# COM-Radio-SBand.net
KiCad netlist of a schematic drawn in Altium Designer
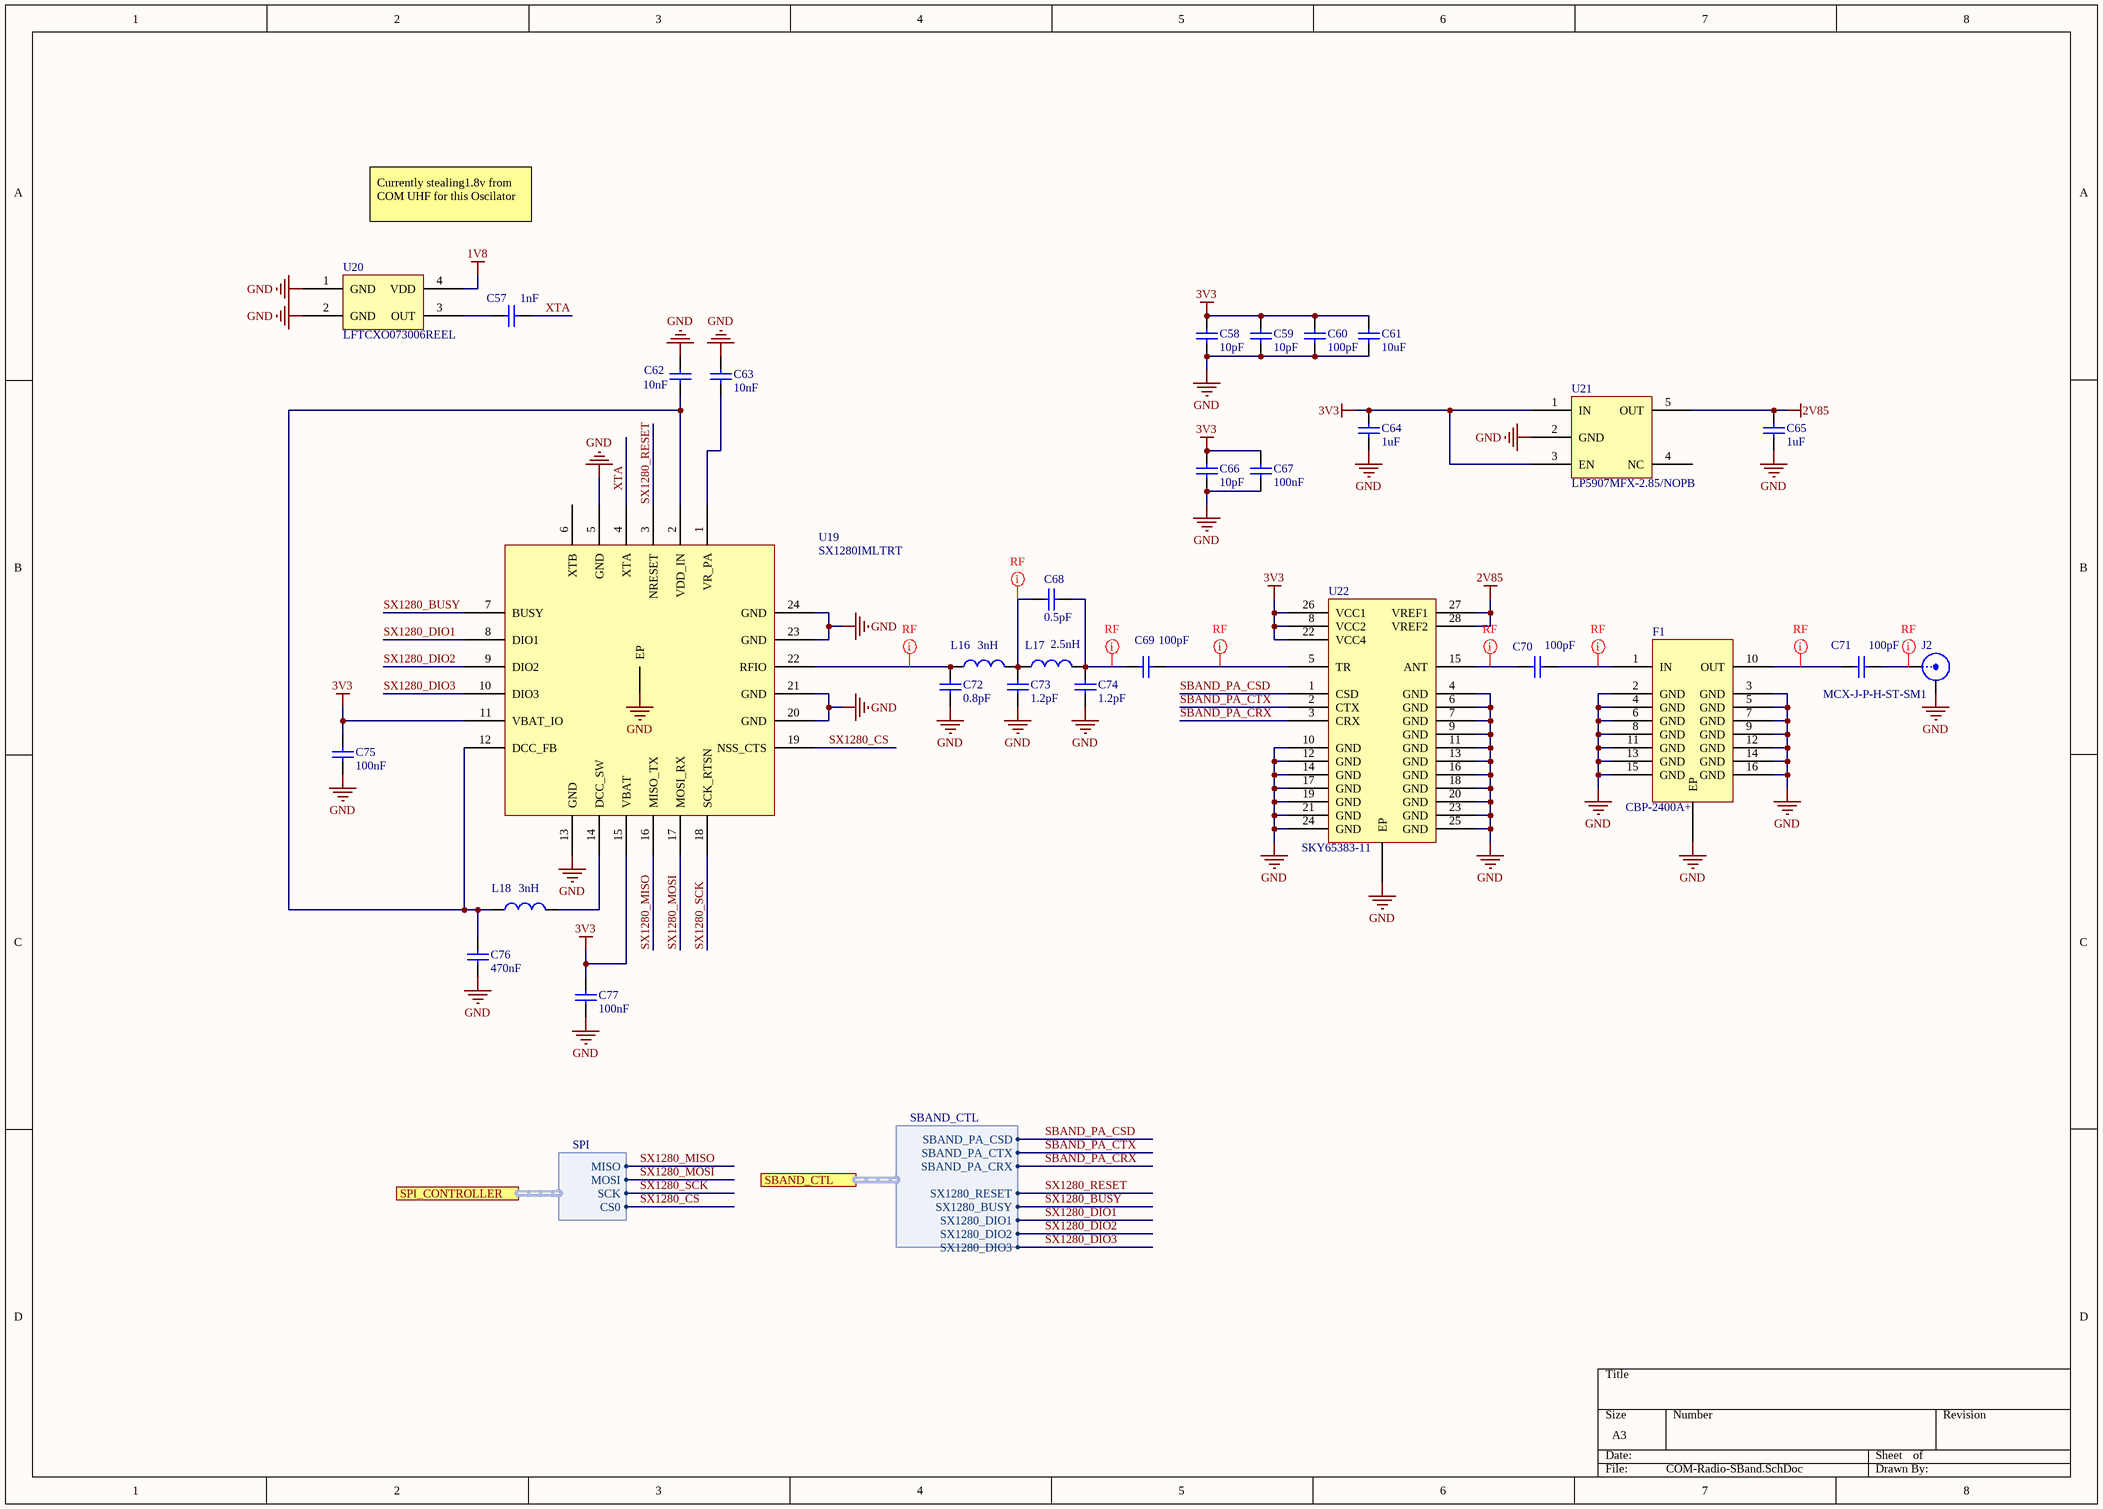
[diagram p0: COM-Radio-SBand.SchDoc]

(export (version "E")
  (design (tool "Eeschema 10.0.6"))
  (components
    (comp (ref "C57")
      (value "CL10B102KA8NNNC")
      (footprint "1608[0603]")
      (description "CAP CER 1000PF 25V X7R 0603")
      (fields
        (field (name "CAPACITANCE") "1nF")
        (field (name "PARTNUMBER") "CBR04C100J5GAC")
        (field (name "MANUFACTURER") "Kemet")
      )
      (libsource (lib "PolarCube") (part "Cap"))
    )
    (comp (ref "C58")
      (value "CL10C100JB8NCNC")
      (footprint "1608[0603]")
      (description "CAP CER 10PF 50V C0G/NP0 0603")
      (fields
        (field (name "CAPACITANCE") "10pF")
        (field (name "PARTNUMBER") "CBR04C100J5GAC")
        (field (name "MANUFACTURER") "Kemet")
      )
      (libsource (lib "PolarCube") (part "Cap"))
    )
    (comp (ref "C59")
      (value "CL10C100JB8NCNC")
      (footprint "1608[0603]")
      (description "CAP CER 10PF 50V C0G/NP0 0603")
      (fields
        (field (name "CAPACITANCE") "10pF")
        (field (name "PARTNUMBER") "CBR04C100J5GAC")
        (field (name "MANUFACTURER") "Kemet")
      )
      (libsource (lib "PolarCube") (part "Cap"))
    )
    (comp (ref "C60")
      (value "500R14N101JV4T")
      (footprint "1608[0603]")
      (description "CAP CER 100PF 50V C0G/NP0 0603")
      (fields
        (field (name "CAPACITANCE") "100pF")
        (field (name "PARTNUMBER") "CBR04C100J5GAC")
        (field (name "MANUFACTURER") "Kemet")
      )
      (libsource (lib "PolarCube") (part "Cap"))
    )
    (comp (ref "C61")
      (value "CL10A106MP8NNNC")
      (footprint "1608[0603]")
      (description "CAP CER 10UF 10V X5R 0603")
      (fields
        (field (name "CAPACITANCE") "10uF")
        (field (name "PARTNUMBER") "CBR04C100J5GAC")
        (field (name "MANUFACTURER") "Kemet")
      )
      (libsource (lib "PolarCube") (part "Cap"))
    )
    (comp (ref "C62")
      (value "CL10B103KB8SFNC")
      (footprint "1608[0603]")
      (description "CAP CER 10000PF 50V X7R 0603")
      (fields
        (field (name "CAPACITANCE") "10nF")
        (field (name "PARTNUMBER") "CBR04C100J5GAC")
        (field (name "MANUFACTURER") "Kemet")
      )
      (libsource (lib "PolarCube") (part "Cap"))
    )
    (comp (ref "C63")
      (value "CL10B103KB8SFNC")
      (footprint "1608[0603]")
      (description "CAP CER 10000PF 50V X7R 0603")
      (fields
        (field (name "CAPACITANCE") "10nF")
        (field (name "PARTNUMBER") "CBR04C100J5GAC")
        (field (name "MANUFACTURER") "Kemet")
      )
      (libsource (lib "PolarCube") (part "Cap"))
    )
    (comp (ref "C64")
      (value "CL10B105MO8NNWC")
      (footprint "1608[0603]")
      (description "CAP CER 1UF 16V X7R 0603")
      (fields
        (field (name "CAPACITANCE") "1uF")
        (field (name "PARTNUMBER") "CGA2B2X7R1H102M050BA")
        (field (name "MANUFACTURER") "TDK")
      )
      (libsource (lib "PolarCube") (part "Cap"))
    )
    (comp (ref "C65")
      (value "CL10B105MO8NNWC")
      (footprint "1608[0603]")
      (description "CAP CER 1UF 16V X7R 0603")
      (fields
        (field (name "CAPACITANCE") "1uF")
        (field (name "PARTNUMBER") "CGA2B2X7R1H102M050BA")
        (field (name "MANUFACTURER") "TDK")
      )
      (libsource (lib "PolarCube") (part "Cap"))
    )
    (comp (ref "C66")
      (value "CL10C100JB8NCNC")
      (footprint "1608[0603]")
      (description "CAP CER 10PF 50V C0G/NP0 0603")
      (fields
        (field (name "CAPACITANCE") "10pF")
        (field (name "PARTNUMBER") "CBR04C100J5GAC")
        (field (name "MANUFACTURER") "Kemet")
      )
      (libsource (lib "PolarCube") (part "Cap"))
    )
    (comp (ref "C67")
      (value "C0603C104J3RACAUTO")
      (footprint "1608[0603]")
      (description "CAP CER 0.1UF 25V X7R 0603")
      (fields
        (field (name "CAPACITANCE") "100nF")
        (field (name "PARTNUMBER") "CBR04C100J5GAC")
        (field (name "MANUFACTURER") "Kemet")
      )
      (libsource (lib "PolarCube") (part "Cap"))
    )
    (comp (ref "C68")
      (value "CBR06C508B5GAC")
      (footprint "1608[0603]")
      (description "CAP CER 0.5PF 50V C0G/NP0 0603")
      (fields
        (field (name "CAPACITANCE") "0.5pF")
        (field (name "PARTNUMBER") "CBR04C100J5GAC")
        (field (name "MANUFACTURER") "Kemet")
      )
      (libsource (lib "PolarCube") (part "Cap"))
    )
    (comp (ref "C69")
      (value "500R14N101JV4T")
      (footprint "1608[0603]")
      (description "CAP CER 100PF 50V C0G/NP0 0603")
      (fields
        (field (name "CAPACITANCE") "100pF")
        (field (name "PARTNUMBER") "CBR04C100J5GAC")
        (field (name "MANUFACTURER") "Kemet")
      )
      (libsource (lib "PolarCube") (part "Cap"))
    )
    (comp (ref "C70")
      (value "500R14N101JV4T")
      (footprint "1608[0603]")
      (description "CAP CER 100PF 50V C0G/NP0 0603")
      (fields
        (field (name "CAPACITANCE") "100pF")
        (field (name "PARTNUMBER") "CGA2B2X7R1H102M050BA")
        (field (name "MANUFACTURER") "TDK")
      )
      (libsource (lib "PolarCube") (part "Cap"))
    )
    (comp (ref "C71")
      (value "500R14N101JV4T")
      (footprint "1608[0603]")
      (description "CAP CER 100PF 50V C0G/NP0 0603")
      (fields
        (field (name "CAPACITANCE") "100pF")
        (field (name "PARTNUMBER") "CGA2B2X7R1H102M050BA")
        (field (name "MANUFACTURER") "TDK")
      )
      (libsource (lib "PolarCube") (part "Cap"))
    )
    (comp (ref "C72")
      (value "CL10C0R8BB8NNNC")
      (footprint "1608[0603]")
      (description "CAP CER 0.8PF 50V C0G/NP0 0603")
      (fields
        (field (name "CAPACITANCE") "0.8pF")
        (field (name "PARTNUMBER") "CBR04C100J5GAC")
        (field (name "MANUFACTURER") "Kemet")
      )
      (libsource (lib "PolarCube") (part "Cap"))
    )
    (comp (ref "C73")
      (value "CL10C1R2BB8NNNC")
      (footprint "1608[0603]")
      (description "CAP CER 1.2PF 50V C0G/NP0 0603")
      (fields
        (field (name "CAPACITANCE") "1.2pF")
        (field (name "PARTNUMBER") "CBR04C100J5GAC")
        (field (name "MANUFACTURER") "Kemet")
      )
      (libsource (lib "PolarCube") (part "Cap"))
    )
    (comp (ref "C74")
      (value "CL10C1R2BB8NNNC")
      (footprint "1608[0603]")
      (description "CAP CER 1.2PF 50V C0G/NP0 0603")
      (fields
        (field (name "CAPACITANCE") "1.2pF")
        (field (name "PARTNUMBER") "CBR04C100J5GAC")
        (field (name "MANUFACTURER") "Kemet")
      )
      (libsource (lib "PolarCube") (part "Cap"))
    )
    (comp (ref "C75")
      (value "C0603C104J3RACAUTO")
      (footprint "1608[0603]")
      (description "CAP CER 0.1UF 25V X7R 0603")
      (fields
        (field (name "CAPACITANCE") "100nF")
        (field (name "PARTNUMBER") "CBR04C100J5GAC")
        (field (name "MANUFACTURER") "Kemet")
      )
      (libsource (lib "PolarCube") (part "Cap"))
    )
    (comp (ref "C76")
      (value "CL10B474KA8NFNC")
      (footprint "1608[0603]")
      (description "CAP CER 0.47UF 25V X7R 0603")
      (fields
        (field (name "CAPACITANCE") "470nF")
        (field (name "PARTNUMBER") "CBR04C100J5GAC")
        (field (name "MANUFACTURER") "Kemet")
      )
      (libsource (lib "PolarCube") (part "Cap"))
    )
    (comp (ref "C77")
      (value "C0603C104J3RACAUTO")
      (footprint "1608[0603]")
      (description "CAP CER 0.1UF 25V X7R 0603")
      (fields
        (field (name "CAPACITANCE") "100nF")
        (field (name "PARTNUMBER") "CBR04C100J5GAC")
        (field (name "MANUFACTURER") "Kemet")
      )
      (libsource (lib "PolarCube") (part "Cap"))
    )
    (comp (ref "F1")
      (value "CBP-2400A+")
      (footprint "CBP-2400A+")
      (libsource (lib "Cesium_3") (part "CBP-2400A+"))
    )
    (comp (ref "J2")
      (value "MCX-J-P-H-ST-SM1")
      (footprint "MCX-J-P-H-ST-SM1")
      (description "MCX Connector Jack, Female Socket 50 Ohm Surface Mount Solder")
      (fields (field (name "PARTNUMBER") "MMCX-J-P-H-RA-TH1"))
      (libsource (lib "UHF-schlib") (part "MMCX-J-P-H-RA-TH1"))
    )
    (comp (ref "L16")
      (value "L-14C3N3SV4T")
      (footprint "1608[0603]")
      (description "FIXED IND 3.3NH 300MA 200 MOHM")
      (fields
        (field (name "INDUCTANCE") "3nH")
        (field (name "PARTNUMBER") "MLG1005SR18JT000")
        (field (name "MANUFACTURER") "TDK")
      )
      (libsource (lib "PolarCube") (part "Inductor"))
    )
    (comp (ref "L17")
      (value "LQW18AN2N4C80D")
      (footprint "1608[0603]")
      (description "FIXED IND 2.4NH 2.4A 26 MOHM SMD")
      (fields
        (field (name "INDUCTANCE") "2.5nH")
        (field (name "PARTNUMBER") "MLG1005SR18JT000")
        (field (name "MANUFACTURER") "TDK")
      )
      (libsource (lib "PolarCube") (part "Inductor"))
    )
    (comp (ref "L18")
      (value "L-14C8N2JV4T")
      (footprint "1608[0603]")
      (description "FIXED IND 8.2NH 300MA 330 MOHM")
      (fields
        (field (name "INDUCTANCE") "3nH")
        (field (name "PARTNUMBER") "MLG1005SR18JT000")
        (field (name "MANUFACTURER") "TDK")
      )
      (libsource (lib "PolarCube") (part "Inductor"))
    )
    (comp (ref "U19")
      (value "SX1280IMLTRT")
      (footprint "QFN50P400X400X80_HS-25N")
      (description "IC RF TxRx Only 802.15.4 LoRa™ 2.4GHz 24-WFQFN Exposed Pad")
      (libsource (lib "Cesium_3") (part "SX1280IMLTRT"))
    )
    (comp (ref "U20")
      (value "LFTCXO073006REEL")
      (footprint "LFTCXO073006REEL")
      (description "50MHz TCXO Clipped Sine Wave Oscillator 2.8 V ~ 3.3 V 4-SMD, No Lead")
      (libsource (lib "Cesium_3") (part "LFTCXO073006REEL"))
    )
    (comp (ref "U21")
      (value "LP5907MFX-2.85/NOPB")
      (footprint "SOT95P280X145-5N")
      (description "Linear Voltage Regulator IC 1 Output 250mA SOT-23-5")
      (libsource (lib "Cesium_3") (part "LP5907MFX-2.85/NOPB"))
    )
    (comp (ref "U22")
      (value "SKY65383-11")
      (footprint "PQFN70P600X600X85_HS-29N")
      (description "RF Front End 2.4GHz ~ 2.483 GHz ISM 28-MCM (6x6)")
      (libsource (lib "Cesium_3") (part "SKY65383-11"))
    )
  )
  (nets
    (net (code "3") (name "/SBAND_PA_CRX") (class "Default")
      (node (ref "U22") (pin "3") (pinfunction "CRX_3") (pintype "passive"))
    )
    (net (code "4") (name "/SBAND_PA_CSD") (class "Default")
      (node (ref "U22") (pin "1") (pinfunction "CSD_1") (pintype "passive"))
    )
    (net (code "5") (name "/SBAND_PA_CTX") (class "Default")
      (node (ref "U22") (pin "2") (pinfunction "CTX_2") (pintype "passive"))
    )
    (net (code "6") (name "/SX1280_BUSY") (class "Default")
      (node (ref "U19") (pin "7") (pinfunction "BUSY_7") (pintype "passive"))
    )
    (net (code "7") (name "/SX1280_CS") (class "Default")
      (node (ref "U19") (pin "19") (pinfunction "NSS_CTS_19") (pintype "passive"))
    )
    (net (code "8") (name "/SX1280_DIO1") (class "Default")
      (node (ref "U19") (pin "8") (pinfunction "DIO1_8") (pintype "passive"))
    )
    (net (code "9") (name "/SX1280_DIO2") (class "Default")
      (node (ref "U19") (pin "9") (pinfunction "DIO2_9") (pintype "passive"))
    )
    (net (code "10") (name "/SX1280_DIO3") (class "Default")
      (node (ref "U19") (pin "10") (pinfunction "DIO3_10") (pintype "passive"))
    )
    (net (code "11") (name "/SX1280_MISO") (class "Default")
      (node (ref "U19") (pin "16") (pinfunction "MISO_TX_16") (pintype "passive"))
    )
    (net (code "12") (name "/SX1280_MOSI") (class "Default")
      (node (ref "U19") (pin "17") (pinfunction "MOSI_RX_17") (pintype "passive"))
    )
    (net (code "13") (name "/SX1280_RESET") (class "Default")
      (node (ref "U19") (pin "3") (pinfunction "NRESET_3") (pintype "passive"))
    )
    (net (code "14") (name "/SX1280_SCK") (class "Default")
      (node (ref "U19") (pin "18") (pinfunction "SCK_RTSN_18") (pintype "passive"))
    )
    (net (code "15") (name "/XTA") (class "Default")
      (node (ref "C57") (pin "1") (pinfunction "1_1") (pintype "passive"))
      (node (ref "U19") (pin "4") (pinfunction "XTA_4") (pintype "passive"))
    )
    (net (code "18") (name "1V8") (class "Default")
      (node (ref "U20") (pin "4") (pinfunction "VDD_4") (pintype "passive"))
    )
    (net (code "19") (name "2V85") (class "Default")
      (node (ref "C65") (pin "2") (pinfunction "2_2") (pintype "passive"))
      (node (ref "U21") (pin "5") (pinfunction "OUT_5") (pintype "passive"))
      (node (ref "U22") (pin "27") (pinfunction "VREF1_27") (pintype "passive"))
      (node (ref "U22") (pin "28") (pinfunction "VREF2_28") (pintype "passive"))
    )
    (net (code "20") (name "3V3") (class "Default")
      (node (ref "C58") (pin "2") (pinfunction "2_2") (pintype "passive"))
      (node (ref "C59") (pin "2") (pinfunction "2_2") (pintype "passive"))
      (node (ref "C60") (pin "2") (pinfunction "2_2") (pintype "passive"))
      (node (ref "C61") (pin "2") (pinfunction "2_2") (pintype "passive"))
      (node (ref "C64") (pin "2") (pinfunction "2_2") (pintype "passive"))
      (node (ref "C66") (pin "2") (pinfunction "2_2") (pintype "passive"))
      (node (ref "C67") (pin "2") (pinfunction "2_2") (pintype "passive"))
      (node (ref "C75") (pin "2") (pinfunction "2_2") (pintype "passive"))
      (node (ref "C77") (pin "2") (pinfunction "2_2") (pintype "passive"))
      (node (ref "U19") (pin "11") (pinfunction "VBAT_IO_11") (pintype "passive"))
      (node (ref "U19") (pin "15") (pinfunction "VBAT_15") (pintype "passive"))
      (node (ref "U21") (pin "1") (pinfunction "IN_1") (pintype "passive"))
      (node (ref "U21") (pin "3") (pinfunction "EN_3") (pintype "passive"))
      (node (ref "U22") (pin "22") (pinfunction "VCC4_22") (pintype "passive"))
      (node (ref "U22") (pin "26") (pinfunction "VCC1_26") (pintype "passive"))
      (node (ref "U22") (pin "8") (pinfunction "VCC2_8") (pintype "passive"))
    )
    (net (code "21") (name "GND") (class "Default")
      (node (ref "C58") (pin "1") (pinfunction "1_1") (pintype "passive"))
      (node (ref "C59") (pin "1") (pinfunction "1_1") (pintype "passive"))
      (node (ref "C60") (pin "1") (pinfunction "1_1") (pintype "passive"))
      (node (ref "C61") (pin "1") (pinfunction "1_1") (pintype "passive"))
      (node (ref "C62") (pin "2") (pinfunction "2_2") (pintype "passive"))
      (node (ref "C63") (pin "2") (pinfunction "2_2") (pintype "passive"))
      (node (ref "C64") (pin "1") (pinfunction "1_1") (pintype "passive"))
      (node (ref "C65") (pin "1") (pinfunction "1_1") (pintype "passive"))
      (node (ref "C66") (pin "1") (pinfunction "1_1") (pintype "passive"))
      (node (ref "C67") (pin "1") (pinfunction "1_1") (pintype "passive"))
      (node (ref "C72") (pin "1") (pinfunction "1_1") (pintype "passive"))
      (node (ref "C73") (pin "1") (pinfunction "1_1") (pintype "passive"))
      (node (ref "C74") (pin "1") (pinfunction "1_1") (pintype "passive"))
      (node (ref "C75") (pin "1") (pinfunction "1_1") (pintype "passive"))
      (node (ref "C76") (pin "1") (pinfunction "1_1") (pintype "passive"))
      (node (ref "C77") (pin "1") (pinfunction "1_1") (pintype "passive"))
      (node (ref "F1") (pin "11") (pinfunction "GND_11") (pintype "passive"))
      (node (ref "F1") (pin "12") (pinfunction "GND_12") (pintype "passive"))
      (node (ref "F1") (pin "13") (pinfunction "GND_13") (pintype "passive"))
      (node (ref "F1") (pin "14") (pinfunction "GND_14") (pintype "passive"))
      (node (ref "F1") (pin "15") (pinfunction "GND_15") (pintype "passive"))
      (node (ref "F1") (pin "16") (pinfunction "GND_16") (pintype "passive"))
      (node (ref "F1") (pin "17") (pinfunction "EP_17") (pintype "passive"))
      (node (ref "F1") (pin "2") (pinfunction "GND_2") (pintype "passive"))
      (node (ref "F1") (pin "3") (pinfunction "GND_3") (pintype "passive"))
      (node (ref "F1") (pin "4") (pinfunction "GND_4") (pintype "passive"))
      (node (ref "F1") (pin "5") (pinfunction "GND_5") (pintype "passive"))
      (node (ref "F1") (pin "6") (pinfunction "GND_6") (pintype "passive"))
      (node (ref "F1") (pin "7") (pinfunction "GND_7") (pintype "passive"))
      (node (ref "F1") (pin "8") (pinfunction "GND_8") (pintype "passive"))
      (node (ref "F1") (pin "9") (pinfunction "GND_9") (pintype "passive"))
      (node (ref "J2") (pin "2") (pinfunction "2_2") (pintype "passive"))
      (node (ref "U19") (pin "13") (pinfunction "GND_13") (pintype "passive"))
      (node (ref "U19") (pin "20") (pinfunction "GND_20") (pintype "passive"))
      (node (ref "U19") (pin "21") (pinfunction "GND_21") (pintype "passive"))
      (node (ref "U19") (pin "23") (pinfunction "GND_23") (pintype "passive"))
      (node (ref "U19") (pin "24") (pinfunction "GND_24") (pintype "passive"))
      (node (ref "U19") (pin "25") (pinfunction "EP_25") (pintype "passive"))
      (node (ref "U19") (pin "5") (pinfunction "GND_5") (pintype "passive"))
      (node (ref "U20") (pin "1") (pinfunction "GND_1") (pintype "passive"))
      (node (ref "U20") (pin "2") (pinfunction "GND_2") (pintype "passive"))
      (node (ref "U21") (pin "2") (pinfunction "GND_2") (pintype "passive"))
      (node (ref "U22") (pin "10") (pinfunction "GND_10") (pintype "passive"))
      (node (ref "U22") (pin "11") (pinfunction "GND_11") (pintype "passive"))
      (node (ref "U22") (pin "12") (pinfunction "GND_12") (pintype "passive"))
      (node (ref "U22") (pin "13") (pinfunction "GND_13") (pintype "passive"))
      (node (ref "U22") (pin "14") (pinfunction "GND_14") (pintype "passive"))
      (node (ref "U22") (pin "16") (pinfunction "GND_16") (pintype "passive"))
      (node (ref "U22") (pin "17") (pinfunction "GND_17") (pintype "passive"))
      (node (ref "U22") (pin "18") (pinfunction "GND_18") (pintype "passive"))
      (node (ref "U22") (pin "19") (pinfunction "GND_19") (pintype "passive"))
      (node (ref "U22") (pin "20") (pinfunction "GND_20") (pintype "passive"))
      (node (ref "U22") (pin "21") (pinfunction "GND_21") (pintype "passive"))
      (node (ref "U22") (pin "23") (pinfunction "GND_23") (pintype "passive"))
      (node (ref "U22") (pin "24") (pinfunction "GND_24") (pintype "passive"))
      (node (ref "U22") (pin "25") (pinfunction "GND_25") (pintype "passive"))
      (node (ref "U22") (pin "29") (pinfunction "EP_29") (pintype "passive"))
      (node (ref "U22") (pin "4") (pinfunction "GND_4") (pintype "passive"))
      (node (ref "U22") (pin "6") (pinfunction "GND_6") (pintype "passive"))
      (node (ref "U22") (pin "7") (pinfunction "GND_7") (pintype "passive"))
      (node (ref "U22") (pin "9") (pinfunction "GND_9") (pintype "passive"))
    )
    (net (code "22") (name "Net-(C68-Pad1)") (class "Default")
      (node (ref "C68") (pin "1") (pinfunction "1_1") (pintype "passive"))
      (node (ref "C69") (pin "2") (pinfunction "2_2") (pintype "passive"))
      (node (ref "C74") (pin "2") (pinfunction "2_2") (pintype "passive"))
      (node (ref "L17") (pin "1") (pinfunction "1_1") (pintype "passive"))
    )
    (net (code "23") (name "Net-(C68-Pad2)") (class "Default")
      (node (ref "C68") (pin "2") (pinfunction "2_2") (pintype "passive"))
      (node (ref "C73") (pin "2") (pinfunction "2_2") (pintype "passive"))
      (node (ref "L16") (pin "1") (pinfunction "1_1") (pintype "passive"))
      (node (ref "L17") (pin "2") (pinfunction "2_2") (pintype "passive"))
    )
    (net (code "24") (name "Net-(C71-Pad2)") (class "Default")
      (node (ref "C71") (pin "2") (pinfunction "2_2") (pintype "passive"))
      (node (ref "J2") (pin "1") (pinfunction "1_1") (pintype "passive"))
    )
    (net (code "25") (name "Net-(F1-IN)") (class "Default")
      (node (ref "C70") (pin "2") (pinfunction "2_2") (pintype "passive"))
      (node (ref "F1") (pin "1") (pinfunction "IN_1") (pintype "passive"))
    )
    (net (code "26") (name "Net-(F1-OUT)") (class "Default")
      (node (ref "C71") (pin "1") (pinfunction "1_1") (pintype "passive"))
      (node (ref "F1") (pin "10") (pinfunction "OUT_10") (pintype "passive"))
    )
    (net (code "27") (name "Net-(U19-DCC_FB)") (class "Default")
      (node (ref "C62") (pin "1") (pinfunction "1_1") (pintype "passive"))
      (node (ref "C76") (pin "2") (pinfunction "2_2") (pintype "passive"))
      (node (ref "L18") (pin "2") (pinfunction "2_2") (pintype "passive"))
      (node (ref "U19") (pin "12") (pinfunction "DCC_FB_12") (pintype "passive"))
      (node (ref "U19") (pin "2") (pinfunction "VDD_IN_2") (pintype "passive"))
    )
    (net (code "28") (name "Net-(U19-DCC_SW)") (class "Default")
      (node (ref "L18") (pin "1") (pinfunction "1_1") (pintype "passive"))
      (node (ref "U19") (pin "14") (pinfunction "DCC_SW_14") (pintype "passive"))
    )
    (net (code "29") (name "Net-(U19-RFIO)") (class "Default")
      (node (ref "C72") (pin "2") (pinfunction "2_2") (pintype "passive"))
      (node (ref "L16") (pin "2") (pinfunction "2_2") (pintype "passive"))
      (node (ref "U19") (pin "22") (pinfunction "RFIO_22") (pintype "passive"))
    )
    (net (code "30") (name "Net-(U19-VR_PA)") (class "Default")
      (node (ref "C63") (pin "1") (pinfunction "1_1") (pintype "passive"))
      (node (ref "U19") (pin "1") (pinfunction "VR_PA_1") (pintype "passive"))
    )
    (net (code "31") (name "Net-(U20-OUT)") (class "Default")
      (node (ref "C57") (pin "2") (pinfunction "2_2") (pintype "passive"))
      (node (ref "U20") (pin "3") (pinfunction "OUT_3") (pintype "passive"))
    )
    (net (code "32") (name "Net-(U22-ANT)") (class "Default")
      (node (ref "C70") (pin "1") (pinfunction "1_1") (pintype "passive"))
      (node (ref "U22") (pin "15") (pinfunction "ANT_15") (pintype "passive"))
    )
    (net (code "33") (name "Net-(U22-TR)") (class "Default")
      (node (ref "C69") (pin "1") (pinfunction "1_1") (pintype "passive"))
      (node (ref "U22") (pin "5") (pinfunction "TR_5") (pintype "passive"))
    )
    (net (code "34") (name "unconnected-(U19-XTB-Pad6)") (class "Default")
      (node (ref "U19") (pin "6") (pinfunction "XTB_6") (pintype "passive"))
    )
    (net (code "35") (name "unconnected-(U21-NC-Pad4)") (class "Default")
      (node (ref "U21") (pin "4") (pinfunction "NC_4") (pintype "passive"))
    )
  )
)
